# BI16_base.net
KiCad netlist of a schematic drawn in EAGLE
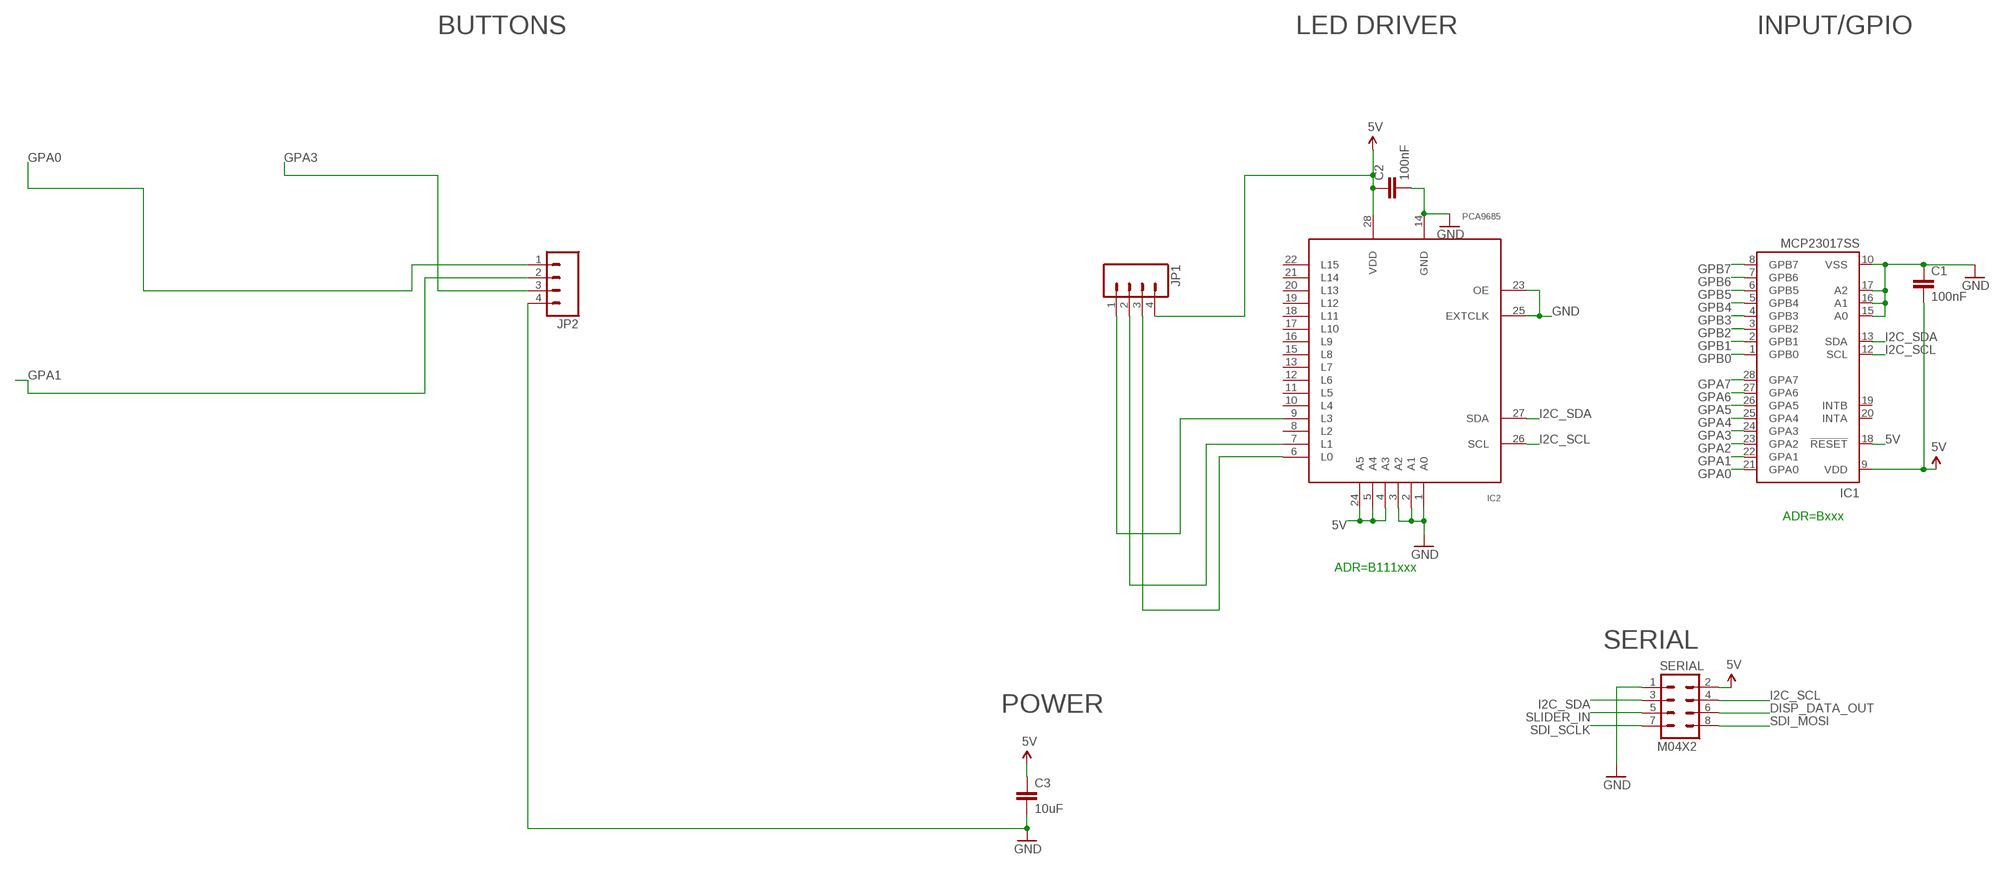
[diagram p0: schematic, sheet 1]

(export (version "E")
  (design (tool "Eeschema 10.0.6"))
  (components
    (comp (ref "C1")
      (value "100nF")
      (footprint "eagle-import:0603-CAP")
      (libsource (lib "eagle-import") (part "CAP0603-CAP"))
    )
    (comp (ref "C2")
      (value "100nF")
      (footprint "eagle-import:0603-CAP")
      (libsource (lib "eagle-import") (part "CAP0603-CAP"))
    )
    (comp (ref "C3")
      (value "10uF")
      (footprint "eagle-import:0805")
      (libsource (lib "eagle-import") (part "CAP0805"))
    )
    (comp (ref "IC1")
      (value "MCP23017SS")
      (footprint "eagle-import:SSOP28")
      (fields
        (field (name "MF") "MICROCHIP")
        (field (name "MPN") "MCP23017-E/SS")
        (field (name "MPN_1") "MCP23017-E/SS")
        (field (name "OC_FARNELL") "1467674")
        (field (name "OC_NEWARK") "31K2960")
      )
      (libsource (lib "eagle-import") (part "MCP23017SS"))
    )
    (comp (ref "IC2")
      (value "PCA9685")
      (footprint "eagle-import:TSSOP28")
      (libsource (lib "eagle-import") (part "PCA9685"))
    )
    (comp (ref "JP1")
      (value "M04LOCK")
      (footprint "eagle-import:1X04_LOCK")
      (libsource (lib "eagle-import") (part "M04LOCK"))
    )
    (comp (ref "JP2")
      (value "M04LOCK")
      (footprint "eagle-import:1X04_LOCK")
      (libsource (lib "eagle-import") (part "M04LOCK"))
    )
    (comp (ref "SERIAL")
      (value "M04X2")
      (footprint "eagle-import:2X4")
      (libsource (lib "eagle-import") (part "M04X2"))
    )
  )
  (nets
    (net (code "1") (name "5V") (class "Default")
      (node (ref "C1") (pin "2") (pinfunction "2_2") (pintype "passive"))
      (node (ref "C2") (pin "1") (pinfunction "1_1") (pintype "passive"))
      (node (ref "C3") (pin "1") (pinfunction "1_1") (pintype "passive"))
      (node (ref "IC1") (pin "18") (pinfunction "~{RESET}_18") (pintype "input"))
      (node (ref "IC1") (pin "9") (pinfunction "VDD_9") (pintype "power_in"))
      (node (ref "IC2") (pin "24") (pinfunction "A5_24") (pintype "input"))
      (node (ref "IC2") (pin "28") (pinfunction "VDD_28") (pintype "power_in"))
      (node (ref "IC2") (pin "4") (pinfunction "A3_4") (pintype "input"))
      (node (ref "IC2") (pin "5") (pinfunction "A4_5") (pintype "input"))
      (node (ref "JP1") (pin "4") (pinfunction "4_4") (pintype "passive"))
      (node (ref "SERIAL") (pin "2") (pinfunction "2_2") (pintype "passive"))
    )
    (net (code "2") (name "DISP_DATA_OUT") (class "Default")
      (node (ref "SERIAL") (pin "6") (pinfunction "6_6") (pintype "passive"))
    )
    (net (code "3") (name "GND") (class "Default")
      (node (ref "C1") (pin "1") (pinfunction "1_1") (pintype "passive"))
      (node (ref "C2") (pin "2") (pinfunction "2_2") (pintype "passive"))
      (node (ref "C3") (pin "2") (pinfunction "2_2") (pintype "passive"))
      (node (ref "IC1") (pin "10") (pinfunction "VSS_10") (pintype "power_in"))
      (node (ref "IC1") (pin "15") (pinfunction "A0_15") (pintype "input"))
      (node (ref "IC1") (pin "16") (pinfunction "A1_16") (pintype "input"))
      (node (ref "IC1") (pin "17") (pinfunction "A2_17") (pintype "input"))
      (node (ref "IC2") (pin "1") (pinfunction "A0_1") (pintype "input"))
      (node (ref "IC2") (pin "14") (pinfunction "GND_14") (pintype "power_in"))
      (node (ref "IC2") (pin "2") (pinfunction "A1_2") (pintype "input"))
      (node (ref "IC2") (pin "23") (pinfunction "OE_23") (pintype "input"))
      (node (ref "IC2") (pin "25") (pinfunction "EXTCLK_25") (pintype "input"))
      (node (ref "IC2") (pin "3") (pinfunction "A2_3") (pintype "input"))
      (node (ref "JP2") (pin "4") (pinfunction "4_4") (pintype "passive"))
      (node (ref "SERIAL") (pin "1") (pinfunction "1_1") (pintype "passive"))
    )
    (net (code "4") (name "GPA0") (class "Default")
      (node (ref "IC1") (pin "21") (pinfunction "GPA0_21") (pintype "bidirectional"))
      (node (ref "JP2") (pin "1") (pinfunction "1_1") (pintype "passive"))
    )
    (net (code "5") (name "GPA1") (class "Default")
      (node (ref "IC1") (pin "22") (pinfunction "GPA1_22") (pintype "bidirectional"))
      (node (ref "JP2") (pin "2") (pinfunction "2_2") (pintype "passive"))
    )
    (net (code "6") (name "GPA2") (class "Default")
      (node (ref "IC1") (pin "23") (pinfunction "GPA2_23") (pintype "bidirectional"))
    )
    (net (code "7") (name "GPA3") (class "Default")
      (node (ref "IC1") (pin "24") (pinfunction "GPA3_24") (pintype "bidirectional"))
      (node (ref "JP2") (pin "3") (pinfunction "3_3") (pintype "passive"))
    )
    (net (code "8") (name "GPA4") (class "Default")
      (node (ref "IC1") (pin "25") (pinfunction "GPA4_25") (pintype "bidirectional"))
    )
    (net (code "9") (name "GPA5") (class "Default")
      (node (ref "IC1") (pin "26") (pinfunction "GPA5_26") (pintype "bidirectional"))
    )
    (net (code "10") (name "GPA6") (class "Default")
      (node (ref "IC1") (pin "27") (pinfunction "GPA6_27") (pintype "bidirectional"))
    )
    (net (code "11") (name "GPA7") (class "Default")
      (node (ref "IC1") (pin "28") (pinfunction "GPA7_28") (pintype "bidirectional"))
    )
    (net (code "12") (name "GPB0") (class "Default")
      (node (ref "IC1") (pin "1") (pinfunction "GPB0_1") (pintype "bidirectional"))
    )
    (net (code "13") (name "GPB1") (class "Default")
      (node (ref "IC1") (pin "2") (pinfunction "GPB1_2") (pintype "bidirectional"))
    )
    (net (code "14") (name "GPB2") (class "Default")
      (node (ref "IC1") (pin "3") (pinfunction "GPB2_3") (pintype "bidirectional"))
    )
    (net (code "15") (name "GPB3") (class "Default")
      (node (ref "IC1") (pin "4") (pinfunction "GPB3_4") (pintype "bidirectional"))
    )
    (net (code "16") (name "GPB4") (class "Default")
      (node (ref "IC1") (pin "5") (pinfunction "GPB4_5") (pintype "bidirectional"))
    )
    (net (code "17") (name "GPB5") (class "Default")
      (node (ref "IC1") (pin "6") (pinfunction "GPB5_6") (pintype "bidirectional"))
    )
    (net (code "18") (name "GPB6") (class "Default")
      (node (ref "IC1") (pin "7") (pinfunction "GPB6_7") (pintype "bidirectional"))
    )
    (net (code "19") (name "GPB7") (class "Default")
      (node (ref "IC1") (pin "8") (pinfunction "GPB7_8") (pintype "bidirectional"))
    )
    (net (code "20") (name "I2C_SCL") (class "Default")
      (node (ref "IC1") (pin "12") (pinfunction "SCL_12") (pintype "input"))
      (node (ref "IC2") (pin "26") (pinfunction "SCL_26") (pintype "input"))
      (node (ref "SERIAL") (pin "4") (pinfunction "4_4") (pintype "passive"))
    )
    (net (code "21") (name "I2C_SDA") (class "Default")
      (node (ref "IC1") (pin "13") (pinfunction "SDA_13") (pintype "bidirectional"))
      (node (ref "IC2") (pin "27") (pinfunction "SDA_27") (pintype "input"))
      (node (ref "SERIAL") (pin "3") (pinfunction "3_3") (pintype "passive"))
    )
    (net (code "22") (name "Net-(IC2-L0)") (class "Default")
      (node (ref "IC2") (pin "6") (pinfunction "L0_6") (pintype "output"))
      (node (ref "JP1") (pin "3") (pinfunction "3_3") (pintype "passive"))
    )
    (net (code "23") (name "Net-(IC2-L1)") (class "Default")
      (node (ref "IC2") (pin "7") (pinfunction "L1_7") (pintype "output"))
      (node (ref "JP1") (pin "2") (pinfunction "2_2") (pintype "passive"))
    )
    (net (code "24") (name "Net-(IC2-L3)") (class "Default")
      (node (ref "IC2") (pin "9") (pinfunction "L3_9") (pintype "output"))
      (node (ref "JP1") (pin "1") (pinfunction "1_1") (pintype "passive"))
    )
    (net (code "25") (name "SDI_MOSI") (class "Default")
      (node (ref "SERIAL") (pin "8") (pinfunction "8_8") (pintype "passive"))
    )
    (net (code "26") (name "SDI_SCLK") (class "Default")
      (node (ref "SERIAL") (pin "7") (pinfunction "7_7") (pintype "passive"))
    )
    (net (code "27") (name "SLIDER_IN") (class "Default")
      (node (ref "SERIAL") (pin "5") (pinfunction "5_5") (pintype "passive"))
    )
    (net (code "28") (name "unconnected-(IC1-INTA-Pad20)") (class "Default")
      (node (ref "IC1") (pin "20") (pinfunction "INTA_20") (pintype "output"))
    )
    (net (code "29") (name "unconnected-(IC1-INTB-Pad19)") (class "Default")
      (node (ref "IC1") (pin "19") (pinfunction "INTB_19") (pintype "output"))
    )
    (net (code "30") (name "unconnected-(IC2-L2-Pad8)") (class "Default")
      (node (ref "IC2") (pin "8") (pinfunction "L2_8") (pintype "output"))
    )
    (net (code "31") (name "unconnected-(IC2-L4-Pad10)") (class "Default")
      (node (ref "IC2") (pin "10") (pinfunction "L4_10") (pintype "output"))
    )
    (net (code "32") (name "unconnected-(IC2-L5-Pad11)") (class "Default")
      (node (ref "IC2") (pin "11") (pinfunction "L5_11") (pintype "output"))
    )
    (net (code "33") (name "unconnected-(IC2-L6-Pad12)") (class "Default")
      (node (ref "IC2") (pin "12") (pinfunction "L6_12") (pintype "output"))
    )
    (net (code "34") (name "unconnected-(IC2-L7-Pad13)") (class "Default")
      (node (ref "IC2") (pin "13") (pinfunction "L7_13") (pintype "output"))
    )
    (net (code "35") (name "unconnected-(IC2-L8-Pad15)") (class "Default")
      (node (ref "IC2") (pin "15") (pinfunction "L8_15") (pintype "output"))
    )
    (net (code "36") (name "unconnected-(IC2-L9-Pad16)") (class "Default")
      (node (ref "IC2") (pin "16") (pinfunction "L9_16") (pintype "output"))
    )
    (net (code "37") (name "unconnected-(IC2-L10-Pad17)") (class "Default")
      (node (ref "IC2") (pin "17") (pinfunction "L10_17") (pintype "output"))
    )
    (net (code "38") (name "unconnected-(IC2-L11-Pad18)") (class "Default")
      (node (ref "IC2") (pin "18") (pinfunction "L11_18") (pintype "output"))
    )
    (net (code "39") (name "unconnected-(IC2-L12-Pad19)") (class "Default")
      (node (ref "IC2") (pin "19") (pinfunction "L12_19") (pintype "output"))
    )
    (net (code "40") (name "unconnected-(IC2-L13-Pad20)") (class "Default")
      (node (ref "IC2") (pin "20") (pinfunction "L13_20") (pintype "output"))
    )
    (net (code "41") (name "unconnected-(IC2-L14-Pad21)") (class "Default")
      (node (ref "IC2") (pin "21") (pinfunction "L14_21") (pintype "output"))
    )
    (net (code "42") (name "unconnected-(IC2-L15-Pad22)") (class "Default")
      (node (ref "IC2") (pin "22") (pinfunction "L15_22") (pintype "output"))
    )
  )
)
